# Wireless_TempSens.net
KiCad netlist of a schematic drawn in EAGLE
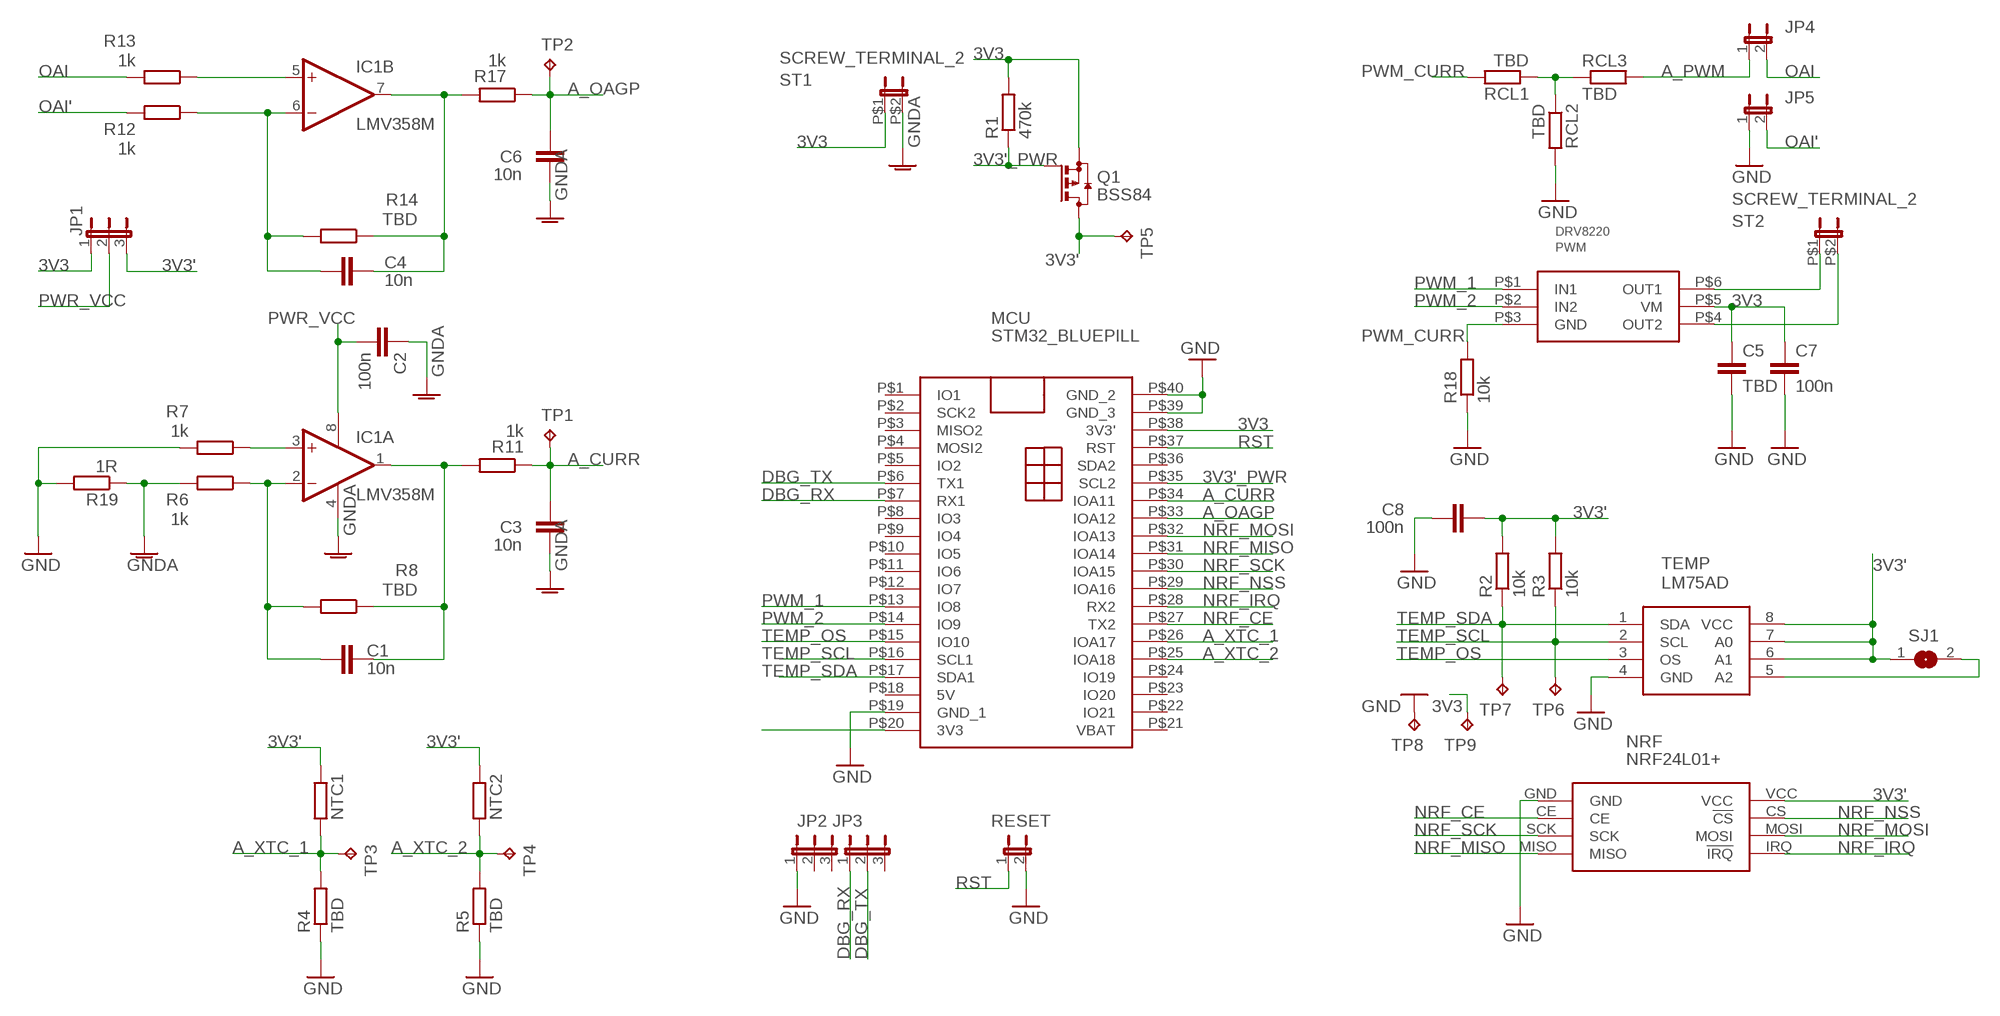
[diagram p0: schematic, sheet 1]

(export (version "E")
  (design (tool "Eeschema 10.0.6"))
  (components
    (comp (ref "C1")
      (value "10n")
      (footprint "eagle-import:C0805")
      (libsource (lib "eagle-import") (part "C-EUC0805"))
    )
    (comp (ref "C2")
      (value "100n")
      (footprint "eagle-import:C0805")
      (libsource (lib "eagle-import") (part "C-EUC0805"))
    )
    (comp (ref "C3")
      (value "10n")
      (footprint "eagle-import:C0805")
      (libsource (lib "eagle-import") (part "C-EUC0805"))
    )
    (comp (ref "C4")
      (value "10n")
      (footprint "eagle-import:C0805")
      (libsource (lib "eagle-import") (part "C-EUC0805"))
    )
    (comp (ref "C5")
      (value "TBD")
      (footprint "eagle-import:C0805")
      (libsource (lib "eagle-import") (part "C-EUC0805"))
    )
    (comp (ref "C6")
      (value "10n")
      (footprint "eagle-import:C0805")
      (libsource (lib "eagle-import") (part "C-EUC0805"))
    )
    (comp (ref "C7")
      (value "100n")
      (footprint "eagle-import:C0805")
      (libsource (lib "eagle-import") (part "C-EUC0805"))
    )
    (comp (ref "C8")
      (value "100n")
      (footprint "eagle-import:C0805")
      (libsource (lib "eagle-import") (part "C-EUC0805"))
    )
    (comp (ref "IC1")
      (value "LMV358M")
      (footprint "eagle-import:SO08")
      (libsource (lib "eagle-import") (part "LMV358?M"))
    )
    (comp (ref "JP1")
      (value "JP2E")
      (footprint "eagle-import:JP2")
      (libsource (lib "eagle-import") (part "JP2E"))
    )
    (comp (ref "JP2")
      (value "JP2E")
      (footprint "eagle-import:JP2")
      (libsource (lib "eagle-import") (part "JP2E"))
    )
    (comp (ref "JP3")
      (value "JP2E")
      (footprint "eagle-import:JP2")
      (libsource (lib "eagle-import") (part "JP2E"))
    )
    (comp (ref "JP4")
      (value "JP1E")
      (footprint "eagle-import:JP1")
      (libsource (lib "eagle-import") (part "JP1E"))
    )
    (comp (ref "JP5")
      (value "JP1E")
      (footprint "eagle-import:JP1")
      (libsource (lib "eagle-import") (part "JP1E"))
    )
    (comp (ref "MCU")
      (value "STM32_BLUEPILL")
      (footprint "eagle-import:STM32_BLUEPILL")
      (libsource (lib "eagle-import") (part "STM32_BLUEPILL"))
    )
    (comp (ref "NRF")
      (value "NRF24L01+")
      (footprint "eagle-import:NRF24L01+")
      (libsource (lib "eagle-import") (part "NRF24L01+"))
    )
    (comp (ref "NTC1")
      (value "R-EU_0204/5")
      (footprint "eagle-import:0204_5")
      (libsource (lib "eagle-import") (part "R-EU_0204/5"))
    )
    (comp (ref "NTC2")
      (value "R-EU_0204/5")
      (footprint "eagle-import:0204_5")
      (libsource (lib "eagle-import") (part "R-EU_0204/5"))
    )
    (comp (ref "PWM")
      (value "DRV8220")
      (footprint "eagle-import:SOT-5X3")
      (libsource (lib "eagle-import") (part "DRV8220"))
    )
    (comp (ref "Q1")
      (value "BSS84")
      (footprint "eagle-import:SOT23")
      (libsource (lib "eagle-import") (part "BSS84"))
    )
    (comp (ref "R1")
      (value "470k")
      (footprint "eagle-import:R0805")
      (libsource (lib "eagle-import") (part "R-EU_R0805"))
    )
    (comp (ref "R2")
      (value "10k")
      (footprint "eagle-import:R0805")
      (libsource (lib "eagle-import") (part "R-EU_R0805"))
    )
    (comp (ref "R3")
      (value "10k")
      (footprint "eagle-import:R0805")
      (libsource (lib "eagle-import") (part "R-EU_R0805"))
    )
    (comp (ref "R4")
      (value "TBD")
      (footprint "eagle-import:R0805")
      (libsource (lib "eagle-import") (part "R-EU_R0805"))
    )
    (comp (ref "R5")
      (value "TBD")
      (footprint "eagle-import:R0805")
      (libsource (lib "eagle-import") (part "R-EU_R0805"))
    )
    (comp (ref "R6")
      (value "1k")
      (footprint "eagle-import:R0805")
      (libsource (lib "eagle-import") (part "R-EU_R0805"))
    )
    (comp (ref "R7")
      (value "1k")
      (footprint "eagle-import:R0805")
      (libsource (lib "eagle-import") (part "R-EU_R0805"))
    )
    (comp (ref "R8")
      (value "TBD")
      (footprint "eagle-import:R0805")
      (libsource (lib "eagle-import") (part "R-EU_R0805"))
    )
    (comp (ref "R11")
      (value "1k")
      (footprint "eagle-import:R0805")
      (libsource (lib "eagle-import") (part "R-EU_R0805"))
    )
    (comp (ref "R12")
      (value "1k")
      (footprint "eagle-import:R0805")
      (libsource (lib "eagle-import") (part "R-EU_R0805"))
    )
    (comp (ref "R13")
      (value "1k")
      (footprint "eagle-import:R0805")
      (libsource (lib "eagle-import") (part "R-EU_R0805"))
    )
    (comp (ref "R14")
      (value "TBD")
      (footprint "eagle-import:R0805")
      (libsource (lib "eagle-import") (part "R-EU_R0805"))
    )
    (comp (ref "R17")
      (value "1k")
      (footprint "eagle-import:R0805")
      (libsource (lib "eagle-import") (part "R-EU_R0805"))
    )
    (comp (ref "R18")
      (value "10k")
      (footprint "eagle-import:R0805")
      (libsource (lib "eagle-import") (part "R-EU_R0805"))
    )
    (comp (ref "R19")
      (value "1R")
      (footprint "eagle-import:R0805")
      (libsource (lib "eagle-import") (part "R-EU_R0805"))
    )
    (comp (ref "RCL1")
      (value "TBD")
      (footprint "eagle-import:R0805")
      (libsource (lib "eagle-import") (part "R-EU_R0805"))
    )
    (comp (ref "RCL2")
      (value "TBD")
      (footprint "eagle-import:R0805")
      (libsource (lib "eagle-import") (part "R-EU_R0805"))
    )
    (comp (ref "RCL3")
      (value "TBD")
      (footprint "eagle-import:R0805")
      (libsource (lib "eagle-import") (part "R-EU_R0805"))
    )
    (comp (ref "RESET")
      (value "JP1E")
      (footprint "eagle-import:JP1")
      (libsource (lib "eagle-import") (part "JP1E"))
    )
    (comp (ref "SJ1") (value "SJ") (footprint "eagle-import:SJ") (libsource (lib "eagle-import") (part "SJ")))
    (comp (ref "ST1")
      (value "SCREW_TERMINAL_2")
      (footprint "eagle-import:SCREW_TERMIANL_2")
      (libsource (lib "eagle-import") (part "SCREW_TERMINAL_2"))
    )
    (comp (ref "ST2")
      (value "SCREW_TERMINAL_2")
      (footprint "eagle-import:SCREW_TERMIANL_2")
      (libsource (lib "eagle-import") (part "SCREW_TERMINAL_2"))
    )
    (comp (ref "TEMP")
      (value "LM75AD")
      (footprint "eagle-import:SOIC8")
      (libsource (lib "eagle-import") (part "LM75AD"))
    )
    (comp (ref "TP1")
      (value "TPPAD1-13")
      (footprint "eagle-import:P1-13")
      (libsource (lib "eagle-import") (part "TPPAD1-13"))
    )
    (comp (ref "TP2")
      (value "TPPAD1-13")
      (footprint "eagle-import:P1-13")
      (libsource (lib "eagle-import") (part "TPPAD1-13"))
    )
    (comp (ref "TP3")
      (value "TPPAD1-13")
      (footprint "eagle-import:P1-13")
      (libsource (lib "eagle-import") (part "TPPAD1-13"))
    )
    (comp (ref "TP4")
      (value "TPPAD1-13")
      (footprint "eagle-import:P1-13")
      (libsource (lib "eagle-import") (part "TPPAD1-13"))
    )
    (comp (ref "TP5")
      (value "TPPAD1-13")
      (footprint "eagle-import:P1-13")
      (libsource (lib "eagle-import") (part "TPPAD1-13"))
    )
    (comp (ref "TP6")
      (value "TPPAD1-13")
      (footprint "eagle-import:P1-13")
      (libsource (lib "eagle-import") (part "TPPAD1-13"))
    )
    (comp (ref "TP7")
      (value "TPPAD1-13")
      (footprint "eagle-import:P1-13")
      (libsource (lib "eagle-import") (part "TPPAD1-13"))
    )
    (comp (ref "TP8")
      (value "TPPAD1-13")
      (footprint "eagle-import:P1-13")
      (libsource (lib "eagle-import") (part "TPPAD1-13"))
    )
    (comp (ref "TP9")
      (value "TPPAD1-13")
      (footprint "eagle-import:P1-13")
      (libsource (lib "eagle-import") (part "TPPAD1-13"))
    )
  )
  (nets
    (net (code "1") (name "/3V3") (class "Default")
      (node (ref "C5") (pin "1") (pinfunction "1_1") (pintype "passive"))
      (node (ref "C7") (pin "1") (pinfunction "1_1") (pintype "passive"))
      (node (ref "JP1") (pin "1") (pinfunction "1_1") (pintype "passive"))
      (node (ref "MCU") (pin "P$20") (pinfunction "3V3_P$20") (pintype "bidirectional"))
      (node (ref "MCU") (pin "P$38") (pinfunction "3V3'_P$38") (pintype "bidirectional"))
      (node (ref "PWM") (pin "P$5") (pinfunction "VM_P$5") (pintype "bidirectional"))
      (node (ref "Q1") (pin "2") (pinfunction "S_2") (pintype "passive"))
      (node (ref "R1") (pin "2") (pinfunction "2_2") (pintype "passive"))
      (node (ref "ST1") (pin "P$1") (pinfunction "1_P$1") (pintype "passive"))
      (node (ref "TP9") (pin "TP") (pinfunction "TP_TP") (pintype "input"))
    )
    (net (code "2") (name "/3V3'") (class "Default")
      (node (ref "C8") (pin "2") (pinfunction "2_2") (pintype "passive"))
      (node (ref "JP1") (pin "3") (pinfunction "3_3") (pintype "passive"))
      (node (ref "NRF") (pin "VCC") (pinfunction "VCC_VCC") (pintype "bidirectional"))
      (node (ref "NTC1") (pin "1") (pinfunction "1_1") (pintype "passive"))
      (node (ref "NTC2") (pin "1") (pinfunction "1_1") (pintype "passive"))
      (node (ref "Q1") (pin "3") (pinfunction "D_3") (pintype "passive"))
      (node (ref "R2") (pin "2") (pinfunction "2_2") (pintype "passive"))
      (node (ref "R3") (pin "2") (pinfunction "2_2") (pintype "passive"))
      (node (ref "SJ1") (pin "1") (pinfunction "1_1") (pintype "passive"))
      (node (ref "TEMP") (pin "6") (pinfunction "A1_6") (pintype "input"))
      (node (ref "TEMP") (pin "7") (pinfunction "A0_7") (pintype "input"))
      (node (ref "TEMP") (pin "8") (pinfunction "VCC_8") (pintype "power_in"))
      (node (ref "TP5") (pin "TP") (pinfunction "TP_TP") (pintype "input"))
    )
    (net (code "3") (name "/3V3'_PWR") (class "Default")
      (node (ref "MCU") (pin "P$35") (pinfunction "SCL2_P$35") (pintype "bidirectional"))
      (node (ref "Q1") (pin "1") (pinfunction "G_1") (pintype "passive"))
      (node (ref "R1") (pin "1") (pinfunction "1_1") (pintype "passive"))
    )
    (net (code "4") (name "/A_CURR") (class "Default")
      (node (ref "C3") (pin "2") (pinfunction "2_2") (pintype "passive"))
      (node (ref "MCU") (pin "P$34") (pinfunction "IOA11_P$34") (pintype "bidirectional"))
      (node (ref "R11") (pin "1") (pinfunction "1_1") (pintype "passive"))
      (node (ref "TP1") (pin "TP") (pinfunction "TP_TP") (pintype "input"))
    )
    (net (code "5") (name "/A_OAGP") (class "Default")
      (node (ref "C6") (pin "2") (pinfunction "2_2") (pintype "passive"))
      (node (ref "MCU") (pin "P$33") (pinfunction "IOA12_P$33") (pintype "bidirectional"))
      (node (ref "R17") (pin "1") (pinfunction "1_1") (pintype "passive"))
      (node (ref "TP2") (pin "TP") (pinfunction "TP_TP") (pintype "input"))
    )
    (net (code "6") (name "/A_PWM") (class "Default")
      (node (ref "JP4") (pin "1") (pinfunction "1_1") (pintype "passive"))
      (node (ref "RCL3") (pin "2") (pinfunction "2_2") (pintype "passive"))
    )
    (net (code "7") (name "/A_XTC_1") (class "Default")
      (node (ref "MCU") (pin "P$26") (pinfunction "IOA17_P$26") (pintype "bidirectional"))
      (node (ref "NTC1") (pin "2") (pinfunction "2_2") (pintype "passive"))
      (node (ref "R4") (pin "2") (pinfunction "2_2") (pintype "passive"))
      (node (ref "TP3") (pin "TP") (pinfunction "TP_TP") (pintype "input"))
    )
    (net (code "8") (name "/A_XTC_2") (class "Default")
      (node (ref "MCU") (pin "P$25") (pinfunction "IOA18_P$25") (pintype "bidirectional"))
      (node (ref "NTC2") (pin "2") (pinfunction "2_2") (pintype "passive"))
      (node (ref "R5") (pin "2") (pinfunction "2_2") (pintype "passive"))
      (node (ref "TP4") (pin "TP") (pinfunction "TP_TP") (pintype "input"))
    )
    (net (code "9") (name "/DBG_RX") (class "Default")
      (node (ref "JP3") (pin "1") (pinfunction "1_1") (pintype "passive"))
      (node (ref "MCU") (pin "P$7") (pinfunction "RX1_P$7") (pintype "bidirectional"))
    )
    (net (code "10") (name "/DBG_TX") (class "Default")
      (node (ref "JP3") (pin "2") (pinfunction "2_2") (pintype "passive"))
      (node (ref "MCU") (pin "P$6") (pinfunction "TX1_P$6") (pintype "bidirectional"))
    )
    (net (code "11") (name "/NRF_CE") (class "Default")
      (node (ref "MCU") (pin "P$27") (pinfunction "TX2_P$27") (pintype "bidirectional"))
      (node (ref "NRF") (pin "CE") (pinfunction "CE_CE") (pintype "bidirectional"))
    )
    (net (code "12") (name "/NRF_IRQ") (class "Default")
      (node (ref "MCU") (pin "P$28") (pinfunction "RX2_P$28") (pintype "bidirectional"))
      (node (ref "NRF") (pin "IRQ") (pinfunction "~{IRQ}_IRQ") (pintype "bidirectional"))
    )
    (net (code "13") (name "/NRF_MISO") (class "Default")
      (node (ref "MCU") (pin "P$31") (pinfunction "IOA14_P$31") (pintype "bidirectional"))
      (node (ref "NRF") (pin "MISO") (pinfunction "MISO_MISO") (pintype "bidirectional"))
    )
    (net (code "14") (name "/NRF_MOSI") (class "Default")
      (node (ref "MCU") (pin "P$32") (pinfunction "IOA13_P$32") (pintype "bidirectional"))
      (node (ref "NRF") (pin "MOSI") (pinfunction "MOSI_MOSI") (pintype "bidirectional"))
    )
    (net (code "15") (name "/NRF_NSS") (class "Default")
      (node (ref "MCU") (pin "P$29") (pinfunction "IOA16_P$29") (pintype "bidirectional"))
      (node (ref "NRF") (pin "CS") (pinfunction "~{CS}_CS") (pintype "bidirectional"))
    )
    (net (code "16") (name "/NRF_SCK") (class "Default")
      (node (ref "MCU") (pin "P$30") (pinfunction "IOA15_P$30") (pintype "bidirectional"))
      (node (ref "NRF") (pin "SCK") (pinfunction "SCK_SCK") (pintype "bidirectional"))
    )
    (net (code "17") (name "/OAI") (class "Default")
      (node (ref "JP4") (pin "2") (pinfunction "2_2") (pintype "passive"))
      (node (ref "R13") (pin "2") (pinfunction "2_2") (pintype "passive"))
    )
    (net (code "18") (name "/OAI'") (class "Default")
      (node (ref "JP5") (pin "2") (pinfunction "2_2") (pintype "passive"))
      (node (ref "R12") (pin "2") (pinfunction "2_2") (pintype "passive"))
    )
    (net (code "19") (name "/PWM_1") (class "Default")
      (node (ref "MCU") (pin "P$13") (pinfunction "IO8_P$13") (pintype "bidirectional"))
      (node (ref "PWM") (pin "P$1") (pinfunction "IN1_P$1") (pintype "bidirectional"))
    )
    (net (code "20") (name "/PWM_2") (class "Default")
      (node (ref "MCU") (pin "P$14") (pinfunction "IO9_P$14") (pintype "bidirectional"))
      (node (ref "PWM") (pin "P$2") (pinfunction "IN2_P$2") (pintype "bidirectional"))
    )
    (net (code "21") (name "/PWM_CURR") (class "Default")
      (node (ref "PWM") (pin "P$3") (pinfunction "GND_P$3") (pintype "bidirectional"))
      (node (ref "R18") (pin "2") (pinfunction "2_2") (pintype "passive"))
      (node (ref "RCL1") (pin "2") (pinfunction "2_2") (pintype "passive"))
    )
    (net (code "22") (name "/PWR_VCC") (class "Default")
      (node (ref "C2") (pin "2") (pinfunction "2_2") (pintype "passive"))
      (node (ref "IC1") (pin "8") (pinfunction "V+_8") (pintype "power_in"))
      (node (ref "JP1") (pin "2") (pinfunction "2_2") (pintype "passive"))
    )
    (net (code "23") (name "/RST") (class "Default")
      (node (ref "MCU") (pin "P$37") (pinfunction "RST_P$37") (pintype "bidirectional"))
      (node (ref "RESET") (pin "1") (pinfunction "1_1") (pintype "passive"))
    )
    (net (code "24") (name "/TEMP_OS") (class "Default")
      (node (ref "MCU") (pin "P$15") (pinfunction "IO10_P$15") (pintype "bidirectional"))
      (node (ref "TEMP") (pin "3") (pinfunction "OS_3") (pintype "output"))
    )
    (net (code "25") (name "/TEMP_SCL") (class "Default")
      (node (ref "MCU") (pin "P$16") (pinfunction "SCL1_P$16") (pintype "bidirectional"))
      (node (ref "R3") (pin "1") (pinfunction "1_1") (pintype "passive"))
      (node (ref "TEMP") (pin "2") (pinfunction "SCL_2") (pintype "input"))
      (node (ref "TP6") (pin "TP") (pinfunction "TP_TP") (pintype "input"))
    )
    (net (code "26") (name "/TEMP_SDA") (class "Default")
      (node (ref "MCU") (pin "P$17") (pinfunction "SDA1_P$17") (pintype "bidirectional"))
      (node (ref "R2") (pin "1") (pinfunction "1_1") (pintype "passive"))
      (node (ref "TEMP") (pin "1") (pinfunction "SDA_1") (pintype "bidirectional"))
      (node (ref "TP7") (pin "TP") (pinfunction "TP_TP") (pintype "input"))
    )
    (net (code "27") (name "GND") (class "Default")
      (node (ref "C5") (pin "2") (pinfunction "2_2") (pintype "passive"))
      (node (ref "C7") (pin "2") (pinfunction "2_2") (pintype "passive"))
      (node (ref "C8") (pin "1") (pinfunction "1_1") (pintype "passive"))
      (node (ref "JP2") (pin "1") (pinfunction "1_1") (pintype "passive"))
      (node (ref "JP5") (pin "1") (pinfunction "1_1") (pintype "passive"))
      (node (ref "MCU") (pin "P$19") (pinfunction "GND_1_P$19") (pintype "bidirectional"))
      (node (ref "MCU") (pin "P$39") (pinfunction "GND_3_P$39") (pintype "bidirectional"))
      (node (ref "MCU") (pin "P$40") (pinfunction "GND_2_P$40") (pintype "bidirectional"))
      (node (ref "NRF") (pin "GND") (pinfunction "GND_GND") (pintype "bidirectional"))
      (node (ref "R18") (pin "1") (pinfunction "1_1") (pintype "passive"))
      (node (ref "R19") (pin "2") (pinfunction "2_2") (pintype "passive"))
      (node (ref "R4") (pin "1") (pinfunction "1_1") (pintype "passive"))
      (node (ref "R5") (pin "1") (pinfunction "1_1") (pintype "passive"))
      (node (ref "R7") (pin "2") (pinfunction "2_2") (pintype "passive"))
      (node (ref "RCL2") (pin "2") (pinfunction "2_2") (pintype "passive"))
      (node (ref "RESET") (pin "2") (pinfunction "2_2") (pintype "passive"))
      (node (ref "TEMP") (pin "4") (pinfunction "GND_4") (pintype "power_in"))
      (node (ref "TP8") (pin "TP") (pinfunction "TP_TP") (pintype "input"))
    )
    (net (code "28") (name "GNDA") (class "Default")
      (node (ref "C2") (pin "1") (pinfunction "1_1") (pintype "passive"))
      (node (ref "C3") (pin "1") (pinfunction "1_1") (pintype "passive"))
      (node (ref "C6") (pin "1") (pinfunction "1_1") (pintype "passive"))
      (node (ref "IC1") (pin "4") (pinfunction "V-_4") (pintype "power_in"))
      (node (ref "R19") (pin "1") (pinfunction "1_1") (pintype "passive"))
      (node (ref "R6") (pin "2") (pinfunction "2_2") (pintype "passive"))
      (node (ref "ST1") (pin "P$2") (pinfunction "2_P$2") (pintype "passive"))
    )
    (net (code "29") (name "Net-(IC1A-+IN)") (class "Default")
      (node (ref "IC1") (pin "3") (pinfunction "+IN_3") (pintype "input"))
      (node (ref "R7") (pin "1") (pinfunction "1_1") (pintype "passive"))
    )
    (net (code "30") (name "Net-(IC1A--IN)") (class "Default")
      (node (ref "C1") (pin "2") (pinfunction "2_2") (pintype "passive"))
      (node (ref "IC1") (pin "2") (pinfunction "-IN_2") (pintype "input"))
      (node (ref "R6") (pin "1") (pinfunction "1_1") (pintype "passive"))
      (node (ref "R8") (pin "2") (pinfunction "2_2") (pintype "passive"))
    )
    (net (code "31") (name "Net-(IC1A-OUT)") (class "Default")
      (node (ref "C1") (pin "1") (pinfunction "1_1") (pintype "passive"))
      (node (ref "IC1") (pin "1") (pinfunction "OUT_1") (pintype "output"))
      (node (ref "R11") (pin "2") (pinfunction "2_2") (pintype "passive"))
      (node (ref "R8") (pin "1") (pinfunction "1_1") (pintype "passive"))
    )
    (net (code "32") (name "Net-(IC1B-+IN)") (class "Default")
      (node (ref "IC1") (pin "5") (pinfunction "+IN_5") (pintype "input"))
      (node (ref "R13") (pin "1") (pinfunction "1_1") (pintype "passive"))
    )
    (net (code "33") (name "Net-(IC1B--IN)") (class "Default")
      (node (ref "C4") (pin "2") (pinfunction "2_2") (pintype "passive"))
      (node (ref "IC1") (pin "6") (pinfunction "-IN_6") (pintype "input"))
      (node (ref "R12") (pin "1") (pinfunction "1_1") (pintype "passive"))
      (node (ref "R14") (pin "2") (pinfunction "2_2") (pintype "passive"))
    )
    (net (code "34") (name "Net-(IC1B-OUT)") (class "Default")
      (node (ref "C4") (pin "1") (pinfunction "1_1") (pintype "passive"))
      (node (ref "IC1") (pin "7") (pinfunction "OUT_7") (pintype "output"))
      (node (ref "R14") (pin "1") (pinfunction "1_1") (pintype "passive"))
      (node (ref "R17") (pin "2") (pinfunction "2_2") (pintype "passive"))
    )
    (net (code "35") (name "Net-(PWM-OUT1)") (class "Default")
      (node (ref "PWM") (pin "P$6") (pinfunction "OUT1_P$6") (pintype "bidirectional"))
      (node (ref "ST2") (pin "P$1") (pinfunction "1_P$1") (pintype "passive"))
    )
    (net (code "36") (name "Net-(PWM-OUT2)") (class "Default")
      (node (ref "PWM") (pin "P$4") (pinfunction "OUT2_P$4") (pintype "bidirectional"))
      (node (ref "ST2") (pin "P$2") (pinfunction "2_P$2") (pintype "passive"))
    )
    (net (code "37") (name "Net-(RCL1-Pad1)") (class "Default")
      (node (ref "RCL1") (pin "1") (pinfunction "1_1") (pintype "passive"))
      (node (ref "RCL2") (pin "1") (pinfunction "1_1") (pintype "passive"))
      (node (ref "RCL3") (pin "1") (pinfunction "1_1") (pintype "passive"))
    )
    (net (code "38") (name "Net-(TEMP-A2)") (class "Default")
      (node (ref "SJ1") (pin "2") (pinfunction "2_2") (pintype "passive"))
      (node (ref "TEMP") (pin "5") (pinfunction "A2_5") (pintype "input"))
    )
    (net (code "39") (name "unconnected-(JP2-Pad2)") (class "Default")
      (node (ref "JP2") (pin "2") (pinfunction "2_2") (pintype "passive"))
    )
    (net (code "40") (name "unconnected-(JP2-Pad3)") (class "Default")
      (node (ref "JP2") (pin "3") (pinfunction "3_3") (pintype "passive"))
    )
    (net (code "41") (name "unconnected-(JP3-Pad3)") (class "Default")
      (node (ref "JP3") (pin "3") (pinfunction "3_3") (pintype "passive"))
    )
    (net (code "42") (name "unconnected-(MCU-5V-PadP$18)") (class "Default")
      (node (ref "MCU") (pin "P$18") (pinfunction "5V_P$18") (pintype "bidirectional"))
    )
    (net (code "43") (name "unconnected-(MCU-IO1-PadP$1)") (class "Default")
      (node (ref "MCU") (pin "P$1") (pinfunction "IO1_P$1") (pintype "bidirectional"))
    )
    (net (code "44") (name "unconnected-(MCU-IO2-PadP$5)") (class "Default")
      (node (ref "MCU") (pin "P$5") (pinfunction "IO2_P$5") (pintype "bidirectional"))
    )
    (net (code "45") (name "unconnected-(MCU-IO3-PadP$8)") (class "Default")
      (node (ref "MCU") (pin "P$8") (pinfunction "IO3_P$8") (pintype "bidirectional"))
    )
    (net (code "46") (name "unconnected-(MCU-IO4-PadP$9)") (class "Default")
      (node (ref "MCU") (pin "P$9") (pinfunction "IO4_P$9") (pintype "bidirectional"))
    )
    (net (code "47") (name "unconnected-(MCU-IO5-PadP$10)") (class "Default")
      (node (ref "MCU") (pin "P$10") (pinfunction "IO5_P$10") (pintype "bidirectional"))
    )
    (net (code "48") (name "unconnected-(MCU-IO6-PadP$11)") (class "Default")
      (node (ref "MCU") (pin "P$11") (pinfunction "IO6_P$11") (pintype "bidirectional"))
    )
    (net (code "49") (name "unconnected-(MCU-IO7-PadP$12)") (class "Default")
      (node (ref "MCU") (pin "P$12") (pinfunction "IO7_P$12") (pintype "bidirectional"))
    )
    (net (code "50") (name "unconnected-(MCU-IO19-PadP$24)") (class "Default")
      (node (ref "MCU") (pin "P$24") (pinfunction "IO19_P$24") (pintype "bidirectional"))
    )
    (net (code "51") (name "unconnected-(MCU-IO20-PadP$23)") (class "Default")
      (node (ref "MCU") (pin "P$23") (pinfunction "IO20_P$23") (pintype "bidirectional"))
    )
    (net (code "52") (name "unconnected-(MCU-IO21-PadP$22)") (class "Default")
      (node (ref "MCU") (pin "P$22") (pinfunction "IO21_P$22") (pintype "bidirectional"))
    )
    (net (code "53") (name "unconnected-(MCU-MISO2-PadP$3)") (class "Default")
      (node (ref "MCU") (pin "P$3") (pinfunction "MISO2_P$3") (pintype "bidirectional"))
    )
    (net (code "54") (name "unconnected-(MCU-MOSI2-PadP$4)") (class "Default")
      (node (ref "MCU") (pin "P$4") (pinfunction "MOSI2_P$4") (pintype "bidirectional"))
    )
    (net (code "55") (name "unconnected-(MCU-SCK2-PadP$2)") (class "Default")
      (node (ref "MCU") (pin "P$2") (pinfunction "SCK2_P$2") (pintype "bidirectional"))
    )
    (net (code "56") (name "unconnected-(MCU-SDA2-PadP$36)") (class "Default")
      (node (ref "MCU") (pin "P$36") (pinfunction "SDA2_P$36") (pintype "bidirectional"))
    )
    (net (code "57") (name "unconnected-(MCU-VBAT-PadP$21)") (class "Default")
      (node (ref "MCU") (pin "P$21") (pinfunction "VBAT_P$21") (pintype "bidirectional"))
    )
  )
)
